# Sheet2.net
KiCad netlist of a schematic drawn in Altium Designer
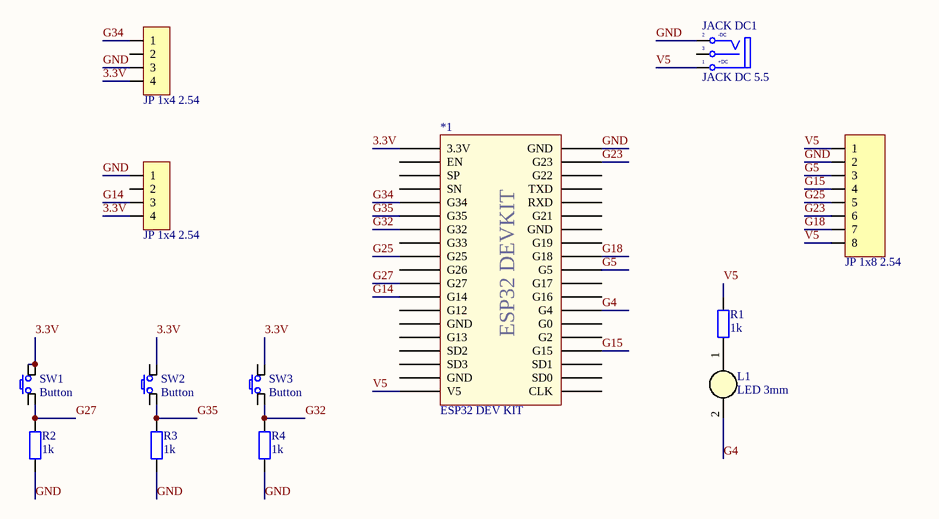
[diagram p0: Sheet2.SchDoc]

(export (version "E")
  (design (tool "Eeschema 10.0.6"))
  (components
    (comp (ref "*1")
      (value "ESP32 DEV KIT")
      (footprint "ESP32 DEVKIT")
      (libsource (lib "Altium_Lib_by_KhueNguyenCreator") (part "ESP32 DEV KIT"))
    )
    (comp (ref "JACK DC1")
      (value "JACK DC 5.5")
      (footprint "JACK DC 5.5")
      (libsource (lib "Altium_Lib_by_KhueNguyenCreator") (part "JACK DC 5.5"))
    )
    (comp (ref "JP1")
      (value "JP 1x4 2.54")
      (footprint "JP 1x4 DT")
      (description "Cắm")
      (libsource (lib "Altium_Lib_by_KhueNguyenCreator") (part "JP 1x4 2.54 Duc Thang"))
    )
    (comp (ref "JP2")
      (value "JP 1x8 2.54")
      (footprint "JP 1x8 DT")
      (description "Cắm")
      (libsource (lib "Altium_Lib_by_KhueNguyenCreator") (part "JP 1x8 2.54 Duc Thang"))
    )
    (comp (ref "JP3")
      (value "JP 1x4 2.54")
      (footprint "JP 1x4 DT")
      (description "Cắm")
      (libsource (lib "Altium_Lib_by_KhueNguyenCreator") (part "JP 1x4 2.54 Duc Thang"))
    )
    (comp (ref "L1")
      (value "LED 3mm")
      (footprint "LED-3MM-WHITE")
      (description "Cắm")
      (libsource (lib "Altium_Lib_by_KhueNguyenCreator") (part "LED 3mm Trang"))
    )
    (comp (ref "R1")
      (value "1k")
      (footprint "tro vach 1/2w")
      (description "Cắm")
      (libsource (lib "Altium_Lib_by_KhueNguyenCreator") (part "Tro Vach 1/2W 5% 1k"))
    )
    (comp (ref "R2")
      (value "1k")
      (footprint "tro vach 1/2w")
      (description "Cắm")
      (libsource (lib "Altium_Lib_by_KhueNguyenCreator") (part "Tro Vach 1/2W 5% 1k"))
    )
    (comp (ref "R3")
      (value "1k")
      (footprint "tro vach 1/2w")
      (description "Cắm")
      (libsource (lib "Altium_Lib_by_KhueNguyenCreator") (part "Tro Vach 1/2W 5% 1k"))
    )
    (comp (ref "R4")
      (value "1k")
      (footprint "tro vach 1/2w")
      (description "Cắm")
      (libsource (lib "Altium_Lib_by_KhueNguyenCreator") (part "Tro Vach 1/2W 5% 1k"))
    )
    (comp (ref "SW1")
      (value "Button")
      (footprint "SW/4/06MM")
      (description "Tact switch 4-pin")
      (libsource (lib "chipfc_altium_libs") (part "SW SPST 4-pin"))
    )
    (comp (ref "SW2")
      (value "Button")
      (footprint "SW/4/06MM")
      (description "Tact switch 4-pin")
      (libsource (lib "chipfc_altium_libs") (part "SW SPST 4-pin"))
    )
    (comp (ref "SW3")
      (value "Button")
      (footprint "SW/4/06MM")
      (description "Tact switch 4-pin")
      (libsource (lib "chipfc_altium_libs") (part "SW SPST 4-pin"))
    )
  )
  (nets
    (net (code "1") (name "/3.3V") (class "Default")
      (node (ref "*1") (pin "1") (pinfunction "3.3V_1") (pintype "passive"))
      (node (ref "JP1") (pin "4") (pinfunction "4_4") (pintype "passive"))
      (node (ref "JP3") (pin "4") (pinfunction "4_4") (pintype "passive"))
      (node (ref "SW1") (pin "3") (pinfunction "3_3") (pintype "passive"))
      (node (ref "SW1") (pin "4") (pinfunction "4_4") (pintype "passive"))
      (node (ref "SW2") (pin "4") (pinfunction "4_4") (pintype "passive"))
      (node (ref "SW3") (pin "4") (pinfunction "4_4") (pintype "passive"))
    )
    (net (code "2") (name "/G4") (class "Default")
      (node (ref "*1") (pin "26") (pinfunction "G4_26") (pintype "passive"))
      (node (ref "L1") (pin "2") (pinfunction "K_2") (pintype "passive"))
    )
    (net (code "3") (name "/G5") (class "Default")
      (node (ref "*1") (pin "29") (pinfunction "G5_29") (pintype "passive"))
      (node (ref "JP2") (pin "3") (pinfunction "3_3") (pintype "passive"))
    )
    (net (code "4") (name "/G14") (class "Default")
      (node (ref "*1") (pin "12") (pinfunction "G14_12") (pintype "passive"))
      (node (ref "JP3") (pin "3") (pinfunction "3_3") (pintype "passive"))
    )
    (net (code "5") (name "/G15") (class "Default")
      (node (ref "*1") (pin "23") (pinfunction "G15_23") (pintype "passive"))
      (node (ref "JP2") (pin "4") (pinfunction "4_4") (pintype "passive"))
    )
    (net (code "6") (name "/G18") (class "Default")
      (node (ref "*1") (pin "30") (pinfunction "G18_30") (pintype "passive"))
      (node (ref "JP2") (pin "7") (pinfunction "7_7") (pintype "passive"))
    )
    (net (code "7") (name "/G23") (class "Default")
      (node (ref "*1") (pin "37") (pinfunction "G23_37") (pintype "passive"))
      (node (ref "JP2") (pin "6") (pinfunction "6_6") (pintype "passive"))
    )
    (net (code "8") (name "/G25") (class "Default")
      (node (ref "*1") (pin "9") (pinfunction "G25_9") (pintype "passive"))
      (node (ref "JP2") (pin "5") (pinfunction "5_5") (pintype "passive"))
    )
    (net (code "9") (name "/G27") (class "Default")
      (node (ref "*1") (pin "11") (pinfunction "G27_11") (pintype "passive"))
      (node (ref "R2") (pin "2") (pinfunction "2_2") (pintype "passive"))
      (node (ref "SW1") (pin "2") (pinfunction "2_2") (pintype "passive"))
    )
    (net (code "10") (name "/G32") (class "Default")
      (node (ref "*1") (pin "7") (pinfunction "G32_7") (pintype "passive"))
      (node (ref "R4") (pin "2") (pinfunction "2_2") (pintype "passive"))
      (node (ref "SW3") (pin "2") (pinfunction "2_2") (pintype "passive"))
    )
    (net (code "11") (name "/G34") (class "Default")
      (node (ref "*1") (pin "5") (pinfunction "G34_5") (pintype "passive"))
      (node (ref "JP1") (pin "1") (pinfunction "1_1") (pintype "passive"))
    )
    (net (code "12") (name "/G35") (class "Default")
      (node (ref "*1") (pin "6") (pinfunction "G35_6") (pintype "passive"))
      (node (ref "R3") (pin "2") (pinfunction "2_2") (pintype "passive"))
      (node (ref "SW2") (pin "2") (pinfunction "2_2") (pintype "passive"))
    )
    (net (code "13") (name "/GND") (class "Default")
      (node (ref "*1") (pin "38") (pinfunction "GND_38") (pintype "passive"))
      (node (ref "JACK DC1") (pin "2") (pinfunction "TN_2") (pintype "passive"))
      (node (ref "JP1") (pin "3") (pinfunction "3_3") (pintype "passive"))
      (node (ref "JP2") (pin "2") (pinfunction "2_2") (pintype "passive"))
      (node (ref "JP3") (pin "1") (pinfunction "1_1") (pintype "passive"))
      (node (ref "R2") (pin "1") (pinfunction "1_1") (pintype "passive"))
      (node (ref "R3") (pin "1") (pinfunction "1_1") (pintype "passive"))
      (node (ref "R4") (pin "1") (pinfunction "1_1") (pintype "passive"))
    )
    (net (code "14") (name "/V5") (class "Default")
      (node (ref "*1") (pin "19") (pinfunction "V5_19") (pintype "passive"))
      (node (ref "JACK DC1") (pin "1") (pinfunction "T_1") (pintype "passive"))
      (node (ref "JP2") (pin "1") (pinfunction "1_1") (pintype "passive"))
      (node (ref "JP2") (pin "8") (pinfunction "8_8") (pintype "passive"))
      (node (ref "R1") (pin "2") (pinfunction "2_2") (pintype "passive"))
    )
    (net (code "15") (name "Net-(L1-A)") (class "Default")
      (node (ref "L1") (pin "1") (pinfunction "A_1") (pintype "passive"))
      (node (ref "R1") (pin "1") (pinfunction "1_1") (pintype "passive"))
    )
    (net (code "16") (name "unconnected-(*1-CLK-Pad20)") (class "Default")
      (node (ref "*1") (pin "20") (pinfunction "CLK_20") (pintype "passive"))
    )
    (net (code "17") (name "unconnected-(*1-EN-Pad2)") (class "Default")
      (node (ref "*1") (pin "2") (pinfunction "EN_2") (pintype "passive"))
    )
    (net (code "18") (name "unconnected-(*1-G0-Pad25)") (class "Default")
      (node (ref "*1") (pin "25") (pinfunction "G0_25") (pintype "passive"))
    )
    (net (code "19") (name "unconnected-(*1-G2-Pad24)") (class "Default")
      (node (ref "*1") (pin "24") (pinfunction "G2_24") (pintype "passive"))
    )
    (net (code "20") (name "unconnected-(*1-G12-Pad13)") (class "Default")
      (node (ref "*1") (pin "13") (pinfunction "G12_13") (pintype "passive"))
    )
    (net (code "21") (name "unconnected-(*1-G13-Pad15)") (class "Default")
      (node (ref "*1") (pin "15") (pinfunction "G13_15") (pintype "passive"))
    )
    (net (code "22") (name "unconnected-(*1-G16-Pad27)") (class "Default")
      (node (ref "*1") (pin "27") (pinfunction "G16_27") (pintype "passive"))
    )
    (net (code "23") (name "unconnected-(*1-G17-Pad28)") (class "Default")
      (node (ref "*1") (pin "28") (pinfunction "G17_28") (pintype "passive"))
    )
    (net (code "24") (name "unconnected-(*1-G19-Pad31)") (class "Default")
      (node (ref "*1") (pin "31") (pinfunction "G19_31") (pintype "passive"))
    )
    (net (code "25") (name "unconnected-(*1-G21-Pad33)") (class "Default")
      (node (ref "*1") (pin "33") (pinfunction "G21_33") (pintype "passive"))
    )
    (net (code "26") (name "unconnected-(*1-G22-Pad36)") (class "Default")
      (node (ref "*1") (pin "36") (pinfunction "G22_36") (pintype "passive"))
    )
    (net (code "27") (name "unconnected-(*1-G26-Pad10)") (class "Default")
      (node (ref "*1") (pin "10") (pinfunction "G26_10") (pintype "passive"))
    )
    (net (code "28") (name "unconnected-(*1-G33-Pad8)") (class "Default")
      (node (ref "*1") (pin "8") (pinfunction "G33_8") (pintype "passive"))
    )
    (net (code "29") (name "unconnected-(*1-GND-Pad14)") (class "Default")
      (node (ref "*1") (pin "14") (pinfunction "GND_14") (pintype "passive"))
    )
    (net (code "30") (name "unconnected-(*1-GND-Pad18)") (class "Default")
      (node (ref "*1") (pin "18") (pinfunction "GND_18") (pintype "passive"))
    )
    (net (code "31") (name "unconnected-(*1-GND-Pad32)") (class "Default")
      (node (ref "*1") (pin "32") (pinfunction "GND_32") (pintype "passive"))
    )
    (net (code "32") (name "unconnected-(*1-RXD-Pad34)") (class "Default")
      (node (ref "*1") (pin "34") (pinfunction "RXD_34") (pintype "passive"))
    )
    (net (code "33") (name "unconnected-(*1-SD0-Pad21)") (class "Default")
      (node (ref "*1") (pin "21") (pinfunction "SD0_21") (pintype "passive"))
    )
    (net (code "34") (name "unconnected-(*1-SD1-Pad22)") (class "Default")
      (node (ref "*1") (pin "22") (pinfunction "SD1_22") (pintype "passive"))
    )
    (net (code "35") (name "unconnected-(*1-SD2-Pad16)") (class "Default")
      (node (ref "*1") (pin "16") (pinfunction "SD2_16") (pintype "passive"))
    )
    (net (code "36") (name "unconnected-(*1-SD3-Pad17)") (class "Default")
      (node (ref "*1") (pin "17") (pinfunction "SD3_17") (pintype "passive"))
    )
    (net (code "37") (name "unconnected-(*1-SN-Pad4)") (class "Default")
      (node (ref "*1") (pin "4") (pinfunction "SN_4") (pintype "passive"))
    )
    (net (code "38") (name "unconnected-(*1-SP-Pad3)") (class "Default")
      (node (ref "*1") (pin "3") (pinfunction "SP_3") (pintype "passive"))
    )
    (net (code "39") (name "unconnected-(*1-TXD-Pad35)") (class "Default")
      (node (ref "*1") (pin "35") (pinfunction "TXD_35") (pintype "passive"))
    )
    (net (code "40") (name "unconnected-(JACK DC1-S-Pad3)") (class "Default")
      (node (ref "JACK DC1") (pin "3") (pinfunction "S_3") (pintype "power_in"))
    )
    (net (code "41") (name "unconnected-(JP1-Pad2)") (class "Default")
      (node (ref "JP1") (pin "2") (pinfunction "2_2") (pintype "passive"))
    )
    (net (code "42") (name "unconnected-(JP3-Pad2)") (class "Default")
      (node (ref "JP3") (pin "2") (pinfunction "2_2") (pintype "passive"))
    )
    (net (code "43") (name "unconnected-(SW1-Pad1)") (class "Default")
      (node (ref "SW1") (pin "1") (pinfunction "1_1") (pintype "passive"))
    )
    (net (code "44") (name "unconnected-(SW2-Pad1)") (class "Default")
      (node (ref "SW2") (pin "1") (pinfunction "1_1") (pintype "passive"))
    )
    (net (code "45") (name "unconnected-(SW2-Pad3)") (class "Default")
      (node (ref "SW2") (pin "3") (pinfunction "3_3") (pintype "passive"))
    )
    (net (code "46") (name "unconnected-(SW3-Pad1)") (class "Default")
      (node (ref "SW3") (pin "1") (pinfunction "1_1") (pintype "passive"))
    )
    (net (code "47") (name "unconnected-(SW3-Pad3)") (class "Default")
      (node (ref "SW3") (pin "3") (pinfunction "3_3") (pintype "passive"))
    )
  )
)
